# sous-vide-shield.net
KiCad netlist of a schematic drawn in EAGLE
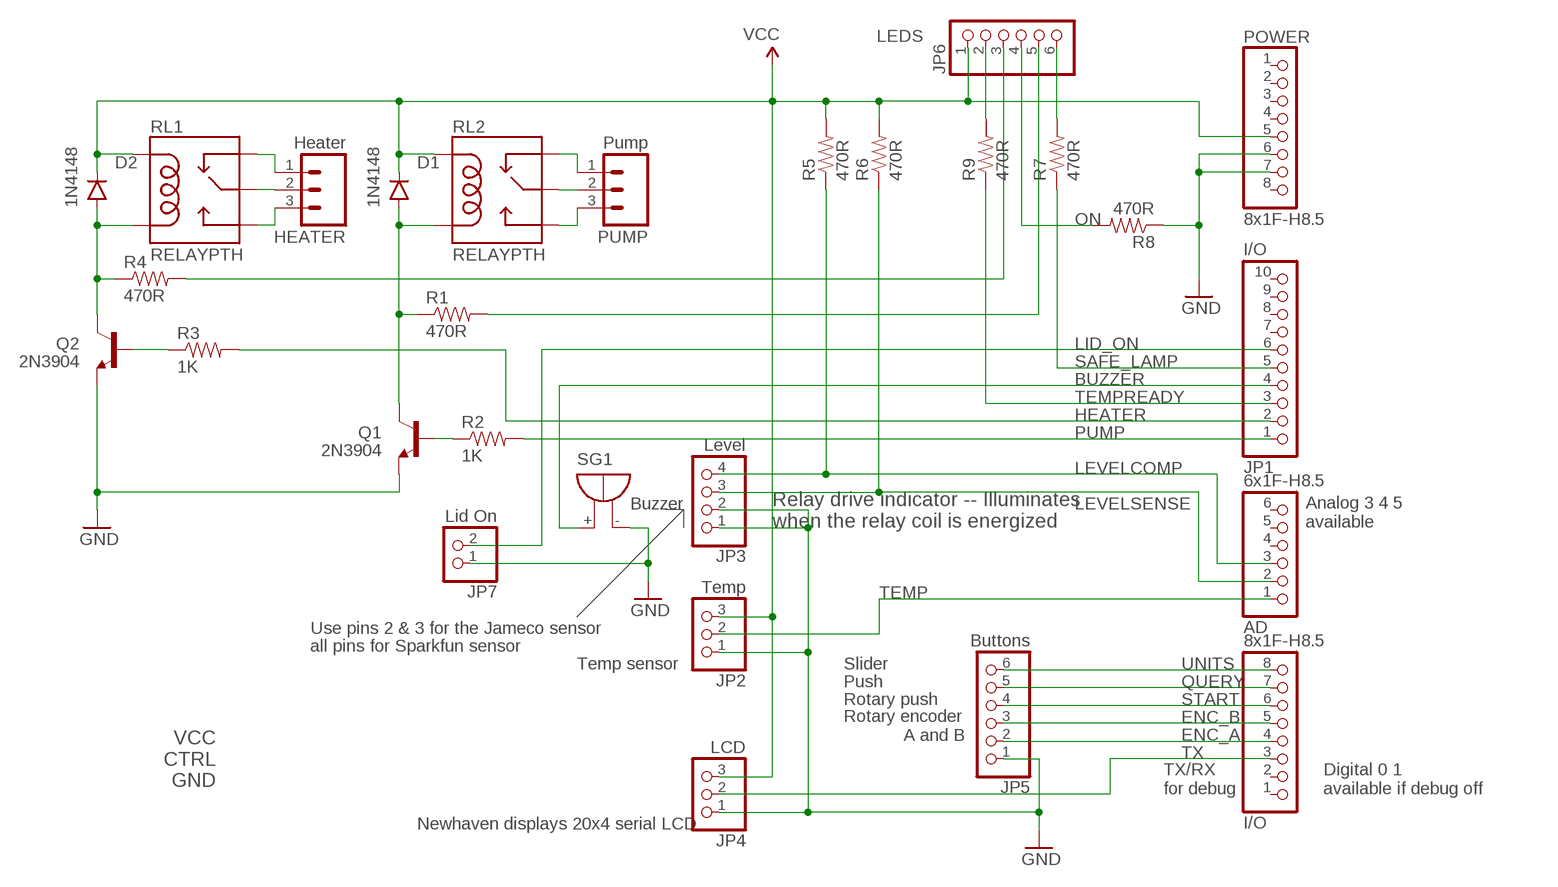
[diagram p0: schematic, sheet 1]

(export (version "E")
  (design (tool "Eeschema 10.0.6"))
  (components
    (comp (ref "AD")
      (value "6x1F-H8.5")
      (footprint "eagle-import:1X06")
      (libsource (lib "eagle-import") (part "PINHD-1X6"))
    )
    (comp (ref "D1")
      (value "1N4148")
      (footprint "eagle-import:DIODE-1N4148-KIT")
      (libsource (lib "eagle-import") (part "DIODEKIT"))
    )
    (comp (ref "D2")
      (value "1N4148")
      (footprint "eagle-import:DIODE-1N4148-KIT")
      (libsource (lib "eagle-import") (part "DIODEKIT"))
    )
    (comp (ref "HEATER")
      (value "Heater")
      (footprint "eagle-import:SCREWTERMINAL-5MM-3")
      (libsource (lib "eagle-import") (part "M03-SCREW-5MM"))
    )
    (comp (ref "I/O")
      (value "8x1F-H8.5")
      (footprint "eagle-import:1X08")
      (libsource (lib "eagle-import") (part "PINHD-1X8"))
    )
    (comp (ref "JP1")
      (value "I/O")
      (footprint "eagle-import:1X10")
      (libsource (lib "eagle-import") (part "PINHD-1X10"))
    )
    (comp (ref "JP2")
      (value "Temp")
      (footprint "eagle-import:1X03")
      (libsource (lib "eagle-import") (part "PINHD-1X3"))
    )
    (comp (ref "JP3")
      (value "Level")
      (footprint "eagle-import:1X04")
      (libsource (lib "eagle-import") (part "PINHD-1X4"))
    )
    (comp (ref "JP4")
      (value "LCD")
      (footprint "eagle-import:1X03")
      (libsource (lib "eagle-import") (part "PINHD-1X3"))
    )
    (comp (ref "JP5")
      (value "Buttons")
      (footprint "eagle-import:1X06")
      (libsource (lib "eagle-import") (part "pinhead_PINHD-1X6"))
    )
    (comp (ref "JP6")
      (value "LEDS")
      (footprint "eagle-import:1X06")
      (libsource (lib "eagle-import") (part "pinhead_PINHD-1X6"))
    )
    (comp (ref "JP7")
      (value "Lid On")
      (footprint "eagle-import:1X02")
      (libsource (lib "eagle-import") (part "PINHD-1X2"))
    )
    (comp (ref "POWER")
      (value "8x1F-H8.5")
      (footprint "eagle-import:1X08")
      (libsource (lib "eagle-import") (part "PINHD-1X8"))
    )
    (comp (ref "PUMP")
      (value "Pump")
      (footprint "eagle-import:SCREWTERMINAL-5MM-3")
      (libsource (lib "eagle-import") (part "M03-SCREW-5MM"))
    )
    (comp (ref "Q1")
      (value "2N3904")
      (footprint "eagle-import:TO-92-EZ")
      (libsource (lib "eagle-import") (part "TRANSISTOR_NPN2N3904-EZ"))
    )
    (comp (ref "Q2")
      (value "2N3904")
      (footprint "eagle-import:TO-92-EZ")
      (libsource (lib "eagle-import") (part "TRANSISTOR_NPN2N3904-EZ"))
    )
    (comp (ref "R1")
      (value "470R")
      (footprint "eagle-import:AXIAL-0.3EZ")
      (libsource (lib "eagle-import") (part "1KOHM-1/4W-1%(PTH)HORIZ-KIT"))
    )
    (comp (ref "R2")
      (value "1K")
      (footprint "eagle-import:AXIAL-0.3EZ")
      (libsource (lib "eagle-import") (part "1KOHM-1/4W-1%(PTH)HORIZ-KIT"))
    )
    (comp (ref "R3")
      (value "1K")
      (footprint "eagle-import:AXIAL-0.3EZ")
      (libsource (lib "eagle-import") (part "1KOHM-1/4W-1%(PTH)HORIZ-KIT"))
    )
    (comp (ref "R4")
      (value "470R")
      (footprint "eagle-import:AXIAL-0.3EZ")
      (libsource (lib "eagle-import") (part "1KOHM-1/4W-1%(PTH)HORIZ-KIT"))
    )
    (comp (ref "R5")
      (value "470R")
      (footprint "eagle-import:AXIAL-0.3EZ")
      (libsource (lib "eagle-import") (part "1KOHM-1/4W-1%(PTH)HORIZ-KIT"))
    )
    (comp (ref "R6")
      (value "470R")
      (footprint "eagle-import:AXIAL-0.3EZ")
      (libsource (lib "eagle-import") (part "1KOHM-1/4W-1%(PTH)HORIZ-KIT"))
    )
    (comp (ref "R7")
      (value "470R")
      (footprint "eagle-import:AXIAL-0.3EZ")
      (libsource (lib "eagle-import") (part "1KOHM-1/4W-1%(PTH)HORIZ-KIT"))
    )
    (comp (ref "R8")
      (value "470R")
      (footprint "eagle-import:AXIAL-0.3EZ")
      (libsource (lib "eagle-import") (part "1KOHM-1/4W-1%(PTH)HORIZ-KIT"))
    )
    (comp (ref "R9")
      (value "470R")
      (footprint "eagle-import:AXIAL-0.3EZ")
      (libsource (lib "eagle-import") (part "1KOHM-1/4W-1%(PTH)HORIZ-KIT"))
    )
    (comp (ref "RL1")
      (value "RELAYPTH")
      (footprint "eagle-import:RELAY-G5Q")
      (libsource (lib "eagle-import") (part "RELAYPTH"))
    )
    (comp (ref "RL2")
      (value "RELAYPTH")
      (footprint "eagle-import:RELAY-G5Q")
      (libsource (lib "eagle-import") (part "RELAYPTH"))
    )
    (comp (ref "SG1")
      (value "Buzzer")
      (footprint "eagle-import:F_TMB")
      (libsource (lib "eagle-import") (part "F/TMB"))
    )
  )
  (nets
    (net (code "1") (name "/BUZZER") (class "Default")
      (node (ref "JP1") (pin "4") (pinfunction "4_4") (pintype "passive"))
      (node (ref "SG1") (pin "+") (pinfunction "+_+") (pintype "passive"))
    )
    (net (code "2") (name "/ENC_A") (class "Default")
      (node (ref "I/O") (pin "4") (pinfunction "4_4") (pintype "passive"))
      (node (ref "JP5") (pin "2") (pinfunction "2_2") (pintype "passive"))
    )
    (net (code "3") (name "/ENC_B") (class "Default")
      (node (ref "I/O") (pin "5") (pinfunction "5_5") (pintype "passive"))
      (node (ref "JP5") (pin "3") (pinfunction "3_3") (pintype "passive"))
    )
    (net (code "4") (name "/HEATER") (class "Default")
      (node (ref "JP1") (pin "2") (pinfunction "2_2") (pintype "passive"))
      (node (ref "R3") (pin "P$2") (pinfunction "2_P$2") (pintype "passive"))
    )
    (net (code "5") (name "/LEVELCOMP") (class "Default")
      (node (ref "AD") (pin "3") (pinfunction "3_3") (pintype "passive"))
      (node (ref "JP3") (pin "4") (pinfunction "4_4") (pintype "passive"))
      (node (ref "R5") (pin "P$1") (pinfunction "1_P$1") (pintype "passive"))
    )
    (net (code "6") (name "/LEVELSENSE") (class "Default")
      (node (ref "AD") (pin "2") (pinfunction "2_2") (pintype "passive"))
      (node (ref "JP3") (pin "3") (pinfunction "3_3") (pintype "passive"))
      (node (ref "R6") (pin "P$1") (pinfunction "1_P$1") (pintype "passive"))
    )
    (net (code "7") (name "/LID_ON") (class "Default")
      (node (ref "JP1") (pin "6") (pinfunction "6_6") (pintype "passive"))
      (node (ref "JP7") (pin "2") (pinfunction "2_2") (pintype "passive"))
    )
    (net (code "8") (name "/ON") (class "Default")
      (node (ref "JP6") (pin "4") (pinfunction "4_4") (pintype "passive"))
      (node (ref "R8") (pin "P$2") (pinfunction "2_P$2") (pintype "passive"))
    )
    (net (code "9") (name "/PUMP") (class "Default")
      (node (ref "JP1") (pin "1") (pinfunction "1_1") (pintype "passive"))
      (node (ref "R2") (pin "P$2") (pinfunction "2_P$2") (pintype "passive"))
    )
    (net (code "10") (name "/QUERY") (class "Default")
      (node (ref "I/O") (pin "7") (pinfunction "7_7") (pintype "passive"))
      (node (ref "JP5") (pin "5") (pinfunction "5_5") (pintype "passive"))
    )
    (net (code "11") (name "/SAFE_LAMP") (class "Default")
      (node (ref "JP1") (pin "5") (pinfunction "5_5") (pintype "passive"))
      (node (ref "R7") (pin "P$1") (pinfunction "1_P$1") (pintype "passive"))
    )
    (net (code "12") (name "/START") (class "Default")
      (node (ref "I/O") (pin "6") (pinfunction "6_6") (pintype "passive"))
      (node (ref "JP5") (pin "4") (pinfunction "4_4") (pintype "passive"))
    )
    (net (code "13") (name "/TEMP") (class "Default")
      (node (ref "AD") (pin "1") (pinfunction "1_1") (pintype "passive"))
      (node (ref "JP2") (pin "2") (pinfunction "2_2") (pintype "passive"))
    )
    (net (code "14") (name "/TEMPREADY") (class "Default")
      (node (ref "JP1") (pin "3") (pinfunction "3_3") (pintype "passive"))
      (node (ref "R9") (pin "P$1") (pinfunction "1_P$1") (pintype "passive"))
    )
    (net (code "15") (name "/TX") (class "Default")
      (node (ref "I/O") (pin "3") (pinfunction "3_3") (pintype "passive"))
      (node (ref "JP4") (pin "2") (pinfunction "2_2") (pintype "passive"))
    )
    (net (code "16") (name "/UNITS") (class "Default")
      (node (ref "I/O") (pin "8") (pinfunction "8_8") (pintype "passive"))
      (node (ref "JP5") (pin "6") (pinfunction "6_6") (pintype "passive"))
    )
    (net (code "17") (name "GND") (class "Default")
      (node (ref "JP2") (pin "1") (pinfunction "1_1") (pintype "passive"))
      (node (ref "JP3") (pin "1") (pinfunction "1_1") (pintype "passive"))
      (node (ref "JP3") (pin "2") (pinfunction "2_2") (pintype "passive"))
      (node (ref "JP4") (pin "1") (pinfunction "1_1") (pintype "passive"))
      (node (ref "JP5") (pin "1") (pinfunction "1_1") (pintype "passive"))
      (node (ref "JP7") (pin "1") (pinfunction "1_1") (pintype "passive"))
      (node (ref "POWER") (pin "6") (pinfunction "6_6") (pintype "passive"))
      (node (ref "POWER") (pin "7") (pinfunction "7_7") (pintype "passive"))
      (node (ref "Q1") (pin "1") (pinfunction "E_1") (pintype "passive"))
      (node (ref "Q2") (pin "1") (pinfunction "E_1") (pintype "passive"))
      (node (ref "R8") (pin "P$1") (pinfunction "1_P$1") (pintype "passive"))
      (node (ref "SG1") (pin "-") (pinfunction "-_-") (pintype "passive"))
    )
    (net (code "18") (name "Net-(Q1-B)") (class "Default")
      (node (ref "Q1") (pin "2") (pinfunction "B_2") (pintype "passive"))
      (node (ref "R2") (pin "P$1") (pinfunction "1_P$1") (pintype "passive"))
    )
    (net (code "19") (name "Net-(Q1-C)") (class "Default")
      (node (ref "D1") (pin "A") (pinfunction "A_A") (pintype "passive"))
      (node (ref "Q1") (pin "3") (pinfunction "C_3") (pintype "passive"))
      (node (ref "R1") (pin "P$1") (pinfunction "1_P$1") (pintype "passive"))
      (node (ref "RL2") (pin "1") (pinfunction "COIL2_1") (pintype "bidirectional"))
    )
    (net (code "20") (name "Net-(Q2-B)") (class "Default")
      (node (ref "Q2") (pin "2") (pinfunction "B_2") (pintype "passive"))
      (node (ref "R3") (pin "P$1") (pinfunction "1_P$1") (pintype "passive"))
    )
    (net (code "21") (name "Net-(Q2-C)") (class "Default")
      (node (ref "D2") (pin "A") (pinfunction "A_A") (pintype "passive"))
      (node (ref "Q2") (pin "3") (pinfunction "C_3") (pintype "passive"))
      (node (ref "R4") (pin "P$1") (pinfunction "1_P$1") (pintype "passive"))
      (node (ref "RL1") (pin "1") (pinfunction "COIL2_1") (pintype "bidirectional"))
    )
    (net (code "22") (name "Net-(R1-2)") (class "Default")
      (node (ref "JP6") (pin "5") (pinfunction "5_5") (pintype "passive"))
      (node (ref "R1") (pin "P$2") (pinfunction "2_P$2") (pintype "passive"))
    )
    (net (code "23") (name "Net-(R4-2)") (class "Default")
      (node (ref "JP6") (pin "3") (pinfunction "3_3") (pintype "passive"))
      (node (ref "R4") (pin "P$2") (pinfunction "2_P$2") (pintype "passive"))
    )
    (net (code "24") (name "Net-(R7-2)") (class "Default")
      (node (ref "JP6") (pin "6") (pinfunction "6_6") (pintype "passive"))
      (node (ref "R7") (pin "P$2") (pinfunction "2_P$2") (pintype "passive"))
    )
    (net (code "25") (name "Net-(R9-2)") (class "Default")
      (node (ref "JP6") (pin "2") (pinfunction "2_2") (pintype "passive"))
      (node (ref "R9") (pin "P$2") (pinfunction "2_P$2") (pintype "passive"))
    )
    (net (code "26") (name "Net-(RL1-MAIN)") (class "Default")
      (node (ref "HEATER") (pin "2") (pinfunction "2_2") (pintype "passive"))
      (node (ref "RL1") (pin "2") (pinfunction "MAIN_2") (pintype "bidirectional"))
    )
    (net (code "27") (name "Net-(RL1-NC)") (class "Default")
      (node (ref "HEATER") (pin "1") (pinfunction "1_1") (pintype "passive"))
      (node (ref "RL1") (pin "4") (pinfunction "NC_4") (pintype "bidirectional"))
    )
    (net (code "28") (name "Net-(RL1-NO)") (class "Default")
      (node (ref "HEATER") (pin "3") (pinfunction "3_3") (pintype "passive"))
      (node (ref "RL1") (pin "3") (pinfunction "NO_3") (pintype "bidirectional"))
    )
    (net (code "29") (name "Net-(RL2-MAIN)") (class "Default")
      (node (ref "PUMP") (pin "2") (pinfunction "2_2") (pintype "passive"))
      (node (ref "RL2") (pin "2") (pinfunction "MAIN_2") (pintype "bidirectional"))
    )
    (net (code "30") (name "Net-(RL2-NC)") (class "Default")
      (node (ref "PUMP") (pin "1") (pinfunction "1_1") (pintype "passive"))
      (node (ref "RL2") (pin "4") (pinfunction "NC_4") (pintype "bidirectional"))
    )
    (net (code "31") (name "Net-(RL2-NO)") (class "Default")
      (node (ref "PUMP") (pin "3") (pinfunction "3_3") (pintype "passive"))
      (node (ref "RL2") (pin "3") (pinfunction "NO_3") (pintype "bidirectional"))
    )
    (net (code "32") (name "VCC") (class "Default")
      (node (ref "D1") (pin "C") (pinfunction "C_C") (pintype "passive"))
      (node (ref "D2") (pin "C") (pinfunction "C_C") (pintype "passive"))
      (node (ref "JP2") (pin "3") (pinfunction "3_3") (pintype "passive"))
      (node (ref "JP4") (pin "3") (pinfunction "3_3") (pintype "passive"))
      (node (ref "JP6") (pin "1") (pinfunction "1_1") (pintype "passive"))
      (node (ref "POWER") (pin "5") (pinfunction "5_5") (pintype "passive"))
      (node (ref "R5") (pin "P$2") (pinfunction "2_P$2") (pintype "passive"))
      (node (ref "R6") (pin "P$2") (pinfunction "2_P$2") (pintype "passive"))
      (node (ref "RL1") (pin "5") (pinfunction "COIL1_5") (pintype "bidirectional"))
      (node (ref "RL2") (pin "5") (pinfunction "COIL1_5") (pintype "bidirectional"))
    )
    (net (code "33") (name "unconnected-(AD-Pad4)") (class "Default")
      (node (ref "AD") (pin "4") (pinfunction "4_4") (pintype "passive"))
    )
    (net (code "34") (name "unconnected-(AD-Pad5)") (class "Default")
      (node (ref "AD") (pin "5") (pinfunction "5_5") (pintype "passive"))
    )
    (net (code "35") (name "unconnected-(AD-Pad6)") (class "Default")
      (node (ref "AD") (pin "6") (pinfunction "6_6") (pintype "passive"))
    )
    (net (code "36") (name "unconnected-(I/O-Pad1)") (class "Default")
      (node (ref "I/O") (pin "1") (pinfunction "1_1") (pintype "passive"))
    )
    (net (code "37") (name "unconnected-(I/O-Pad2)") (class "Default")
      (node (ref "I/O") (pin "2") (pinfunction "2_2") (pintype "passive"))
    )
    (net (code "38") (name "unconnected-(JP1-Pad7)") (class "Default")
      (node (ref "JP1") (pin "7") (pinfunction "7_7") (pintype "passive"))
    )
    (net (code "39") (name "unconnected-(JP1-Pad8)") (class "Default")
      (node (ref "JP1") (pin "8") (pinfunction "8_8") (pintype "passive"))
    )
    (net (code "40") (name "unconnected-(JP1-Pad9)") (class "Default")
      (node (ref "JP1") (pin "9") (pinfunction "9_9") (pintype "passive"))
    )
    (net (code "41") (name "unconnected-(JP1-Pad10)") (class "Default")
      (node (ref "JP1") (pin "10") (pinfunction "10_10") (pintype "passive"))
    )
    (net (code "42") (name "unconnected-(POWER-Pad1)") (class "Default")
      (node (ref "POWER") (pin "1") (pinfunction "1_1") (pintype "passive"))
    )
    (net (code "43") (name "unconnected-(POWER-Pad2)") (class "Default")
      (node (ref "POWER") (pin "2") (pinfunction "2_2") (pintype "passive"))
    )
    (net (code "44") (name "unconnected-(POWER-Pad3)") (class "Default")
      (node (ref "POWER") (pin "3") (pinfunction "3_3") (pintype "passive"))
    )
    (net (code "45") (name "unconnected-(POWER-Pad4)") (class "Default")
      (node (ref "POWER") (pin "4") (pinfunction "4_4") (pintype "passive"))
    )
    (net (code "46") (name "unconnected-(POWER-Pad8)") (class "Default")
      (node (ref "POWER") (pin "8") (pinfunction "8_8") (pintype "passive"))
    )
  )
)
